# MCU.net
KiCad netlist of a schematic drawn in Altium Designer
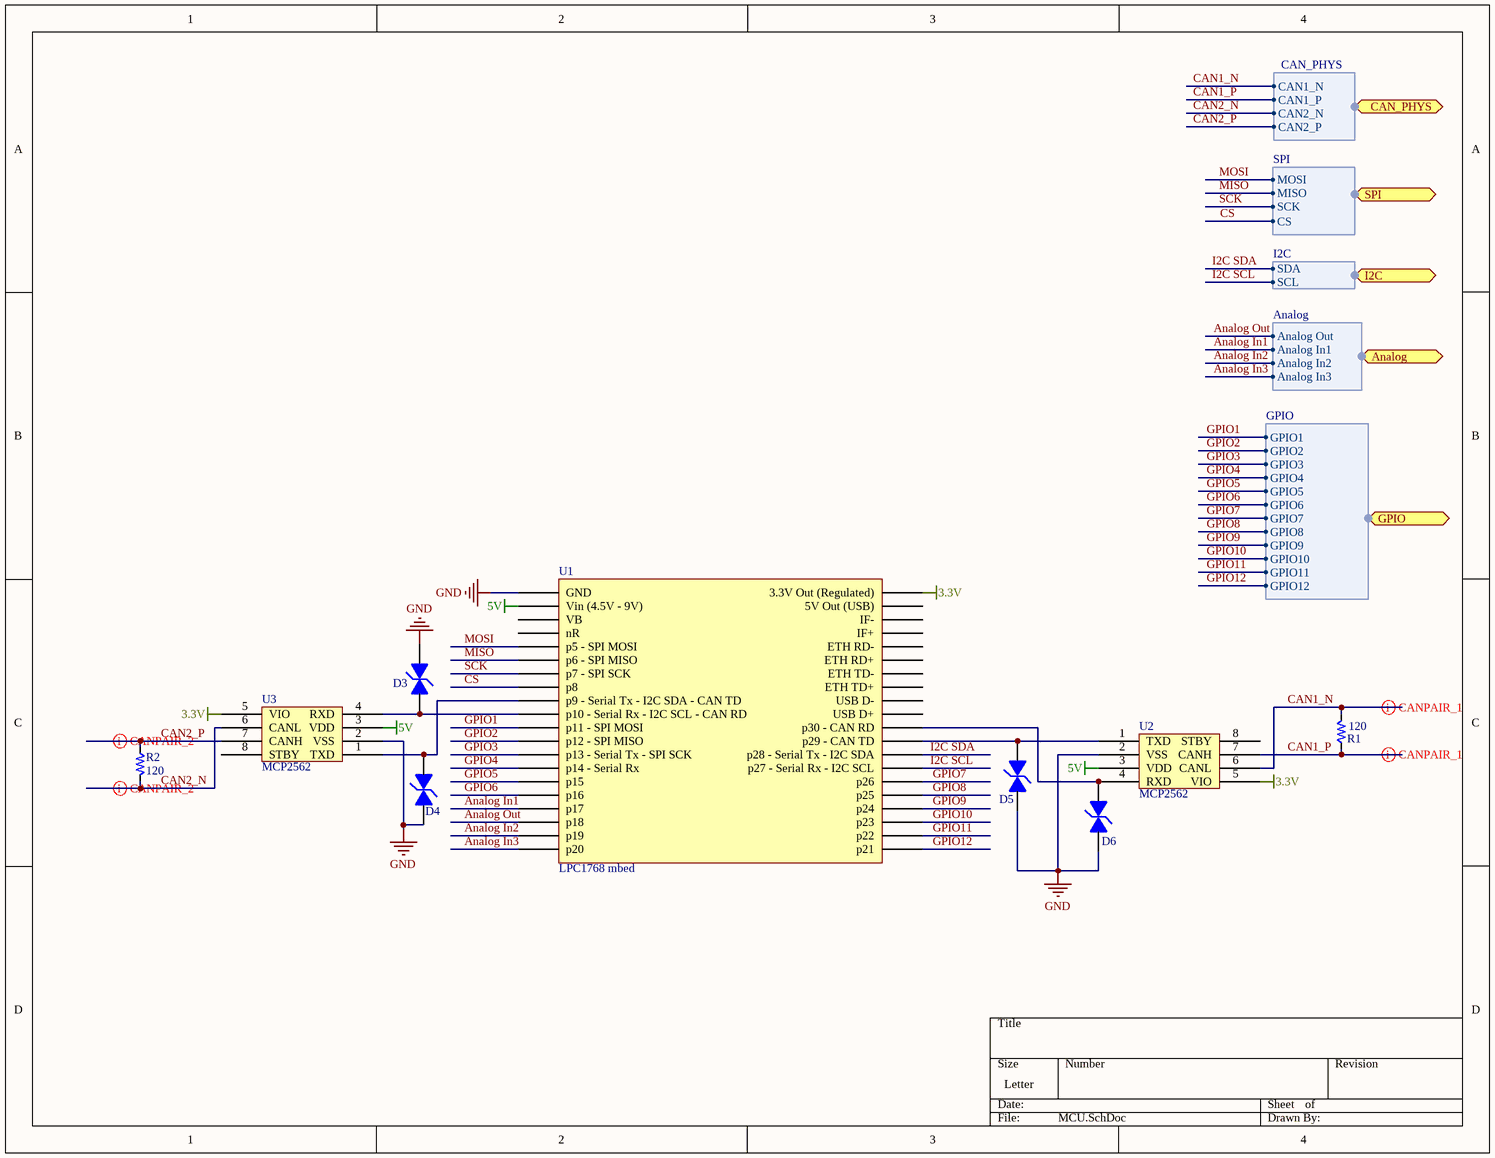
[diagram p0: MCU.SchDoc]

(export (version "E")
  (design (tool "Eeschema 10.0.6"))
  (components
    (comp (ref "D3")
      (value "TVS Diode")
      (footprint "TVS Diode")
      (fields (field (name "MANUFACTURER") "Bourns"))
      (libsource (lib "TVS Diode") (part "TVS Diode"))
    )
    (comp (ref "D4")
      (value "TVS Diode")
      (footprint "TVS Diode")
      (fields (field (name "MANUFACTURER") "Bourns"))
      (libsource (lib "TVS Diode") (part "TVS Diode"))
    )
    (comp (ref "D5")
      (value "TVS Diode")
      (footprint "TVS Diode")
      (fields (field (name "MANUFACTURER") "Bourns"))
      (libsource (lib "TVS Diode") (part "TVS Diode"))
    )
    (comp (ref "D6")
      (value "TVS Diode")
      (footprint "TVS Diode")
      (fields (field (name "MANUFACTURER") "Bourns"))
      (libsource (lib "TVS Diode") (part "TVS Diode"))
    )
    (comp (ref "R1")
      (value "120")
      (footprint "PCB_GENERIC_SMD_0603")
      (description "120 Ohms")
      (libsource (lib "SCH_GENERIC_RESISTOR_0603") (part "SCH_GENERIC_RESISTOR_0603"))
    )
    (comp (ref "R2")
      (value "120")
      (footprint "PCB_GENERIC_SMD_0603")
      (description "120 Ohms")
      (libsource (lib "SCH_GENERIC_RESISTOR_0603") (part "SCH_GENERIC_RESISTOR_0603"))
    )
    (comp (ref "U1")
      (value "LPC1768 mbed")
      (footprint "LPC 1768 mbed Layout")
      (libsource (lib "LPC1768_mbed_SCH") (part "LPC1768 mbed"))
    )
    (comp (ref "U2") (value "MCP2562") (footprint "MCP2562") (libsource (lib "") (part "MCP2562_1")))
    (comp (ref "U3") (value "MCP2562") (footprint "MCP2562") (libsource (lib "MCP2562_SCH") (part "MCP2562")))
  )
  (nets
    (net (code "6") (name "/Analog In1") (class "Default")
      (node (ref "U1") (pin "17") (pinfunction "p17_17") (pintype "passive"))
    )
    (net (code "7") (name "/Analog In2") (class "Default")
      (node (ref "U1") (pin "19") (pinfunction "p19_19") (pintype "passive"))
    )
    (net (code "8") (name "/Analog In3") (class "Default")
      (node (ref "U1") (pin "20") (pinfunction "p20_20") (pintype "passive"))
    )
    (net (code "9") (name "/Analog Out") (class "Default")
      (node (ref "U1") (pin "18") (pinfunction "p18_18") (pintype "passive"))
    )
    (net (code "10") (name "/CAN1_N") (class "Default")
      (node (ref "R1") (pin "2") (pinfunction "2_2") (pintype "passive"))
      (node (ref "U2") (pin "6") (pinfunction "CANL_6") (pintype "passive"))
    )
    (net (code "11") (name "/CAN1_P") (class "Default")
      (node (ref "R1") (pin "1") (pinfunction "1_1") (pintype "passive"))
      (node (ref "U2") (pin "7") (pinfunction "CANH_7") (pintype "passive"))
    )
    (net (code "12") (name "/CAN2_N") (class "Default")
      (node (ref "R2") (pin "2") (pinfunction "2_2") (pintype "passive"))
      (node (ref "U3") (pin "6") (pinfunction "CANL_6") (pintype "passive"))
    )
    (net (code "13") (name "/CAN2_P") (class "Default")
      (node (ref "R2") (pin "1") (pinfunction "1_1") (pintype "passive"))
      (node (ref "U3") (pin "7") (pinfunction "CANH_7") (pintype "passive"))
    )
    (net (code "14") (name "/CS") (class "Default")
      (node (ref "U1") (pin "8") (pinfunction "p8_8") (pintype "passive"))
    )
    (net (code "15") (name "/GPIO1") (class "Default")
      (node (ref "U1") (pin "11") (pinfunction "p11_-_SPI_MOSI_11") (pintype "passive"))
    )
    (net (code "16") (name "/GPIO2") (class "Default")
      (node (ref "U1") (pin "12") (pinfunction "p12_-_SPI_MISO_12") (pintype "passive"))
    )
    (net (code "17") (name "/GPIO3") (class "Default")
      (node (ref "U1") (pin "13") (pinfunction "p13_-_Serial_Tx_-_SPI_SCK_13") (pintype "passive"))
    )
    (net (code "18") (name "/GPIO4") (class "Default")
      (node (ref "U1") (pin "14") (pinfunction "p14_-_Serial_Rx_14") (pintype "passive"))
    )
    (net (code "19") (name "/GPIO5") (class "Default")
      (node (ref "U1") (pin "15") (pinfunction "p15_15") (pintype "passive"))
    )
    (net (code "20") (name "/GPIO6") (class "Default")
      (node (ref "U1") (pin "16") (pinfunction "p16_16") (pintype "passive"))
    )
    (net (code "21") (name "/GPIO7") (class "Default")
      (node (ref "U1") (pin "26") (pinfunction "p26_26") (pintype "passive"))
    )
    (net (code "22") (name "/GPIO8") (class "Default")
      (node (ref "U1") (pin "25") (pinfunction "p25_25") (pintype "passive"))
    )
    (net (code "23") (name "/GPIO9") (class "Default")
      (node (ref "U1") (pin "24") (pinfunction "p24_24") (pintype "passive"))
    )
    (net (code "24") (name "/GPIO10") (class "Default")
      (node (ref "U1") (pin "23") (pinfunction "p23_23") (pintype "passive"))
    )
    (net (code "25") (name "/GPIO11") (class "Default")
      (node (ref "U1") (pin "22") (pinfunction "p22_22") (pintype "passive"))
    )
    (net (code "26") (name "/GPIO12") (class "Default")
      (node (ref "U1") (pin "21") (pinfunction "p21_21") (pintype "passive"))
    )
    (net (code "27") (name "/I2C SCL") (class "Default")
      (node (ref "U1") (pin "27") (pinfunction "p27_-_Serial_Rx_-_I2C_SCL_27") (pintype "passive"))
    )
    (net (code "28") (name "/I2C SDA") (class "Default")
      (node (ref "U1") (pin "28") (pinfunction "p28_-_Serial_Tx_-_I2C_SDA_28") (pintype "passive"))
    )
    (net (code "29") (name "/MISO") (class "Default")
      (node (ref "U1") (pin "6") (pinfunction "p6_-_SPI_MISO_6") (pintype "passive"))
    )
    (net (code "30") (name "/MOSI") (class "Default")
      (node (ref "U1") (pin "5") (pinfunction "p5_-_SPI_MOSI_5") (pintype "passive"))
    )
    (net (code "31") (name "/SCK") (class "Default")
      (node (ref "U1") (pin "7") (pinfunction "p7_-_SPI_SCK_7") (pintype "passive"))
    )
    (net (code "37") (name "3.3V") (class "Default")
      (node (ref "U1") (pin "40") (pinfunction "3.3V_Out_(Regulated)_40") (pintype "passive"))
      (node (ref "U2") (pin "5") (pinfunction "VIO_5") (pintype "passive"))
      (node (ref "U3") (pin "5") (pinfunction "VIO_5") (pintype "passive"))
    )
    (net (code "38") (name "5V") (class "Default")
      (node (ref "U1") (pin "2") (pinfunction "Vin_(4.5V_-_9V)_2") (pintype "passive"))
      (node (ref "U2") (pin "3") (pinfunction "VDD_3") (pintype "passive"))
      (node (ref "U3") (pin "3") (pinfunction "VDD_3") (pintype "passive"))
    )
    (net (code "39") (name "GND") (class "Default")
      (node (ref "D3") (pin "2") (pintype "passive"))
      (node (ref "D4") (pin "2") (pintype "passive"))
      (node (ref "D5") (pin "1") (pintype "passive"))
      (node (ref "D6") (pin "1") (pintype "passive"))
      (node (ref "U1") (pin "1") (pinfunction "GND_1") (pintype "passive"))
      (node (ref "U2") (pin "2") (pinfunction "VSS_2") (pintype "passive"))
      (node (ref "U3") (pin "2") (pinfunction "VSS_2") (pintype "passive"))
    )
    (net (code "40") (name "Net-(U1-p9_-_Serial_Tx_-_I2C_SDA_-_CAN_TD)") (class "Default")
      (node (ref "D4") (pin "1") (pintype "passive"))
      (node (ref "U1") (pin "9") (pinfunction "p9_-_Serial_Tx_-_I2C_SDA_-_CAN_TD_9") (pintype "passive"))
      (node (ref "U3") (pin "1") (pinfunction "TXD_1") (pintype "passive"))
    )
    (net (code "41") (name "Net-(U1-p10_-_Serial_Rx_-_I2C_SCL_-_CAN_RD)") (class "Default")
      (node (ref "D3") (pin "1") (pintype "passive"))
      (node (ref "U1") (pin "10") (pinfunction "p10_-_Serial_Rx_-_I2C_SCL_-_CAN_RD_10") (pintype "passive"))
      (node (ref "U3") (pin "4") (pinfunction "RXD_4") (pintype "passive"))
    )
    (net (code "42") (name "Net-(U1-p29_-_CAN_TD)") (class "Default")
      (node (ref "D5") (pin "2") (pintype "passive"))
      (node (ref "U1") (pin "29") (pinfunction "p29_-_CAN_TD_29") (pintype "passive"))
      (node (ref "U2") (pin "1") (pinfunction "TXD_1") (pintype "passive"))
    )
    (net (code "43") (name "Net-(U1-p30_-_CAN_RD)") (class "Default")
      (node (ref "D6") (pin "2") (pintype "passive"))
      (node (ref "U1") (pin "30") (pinfunction "p30_-_CAN_RD_30") (pintype "passive"))
      (node (ref "U2") (pin "4") (pinfunction "RXD_4") (pintype "passive"))
    )
    (net (code "44") (name "unconnected-(U1-5V_Out_(USB)-Pad39)") (class "Default")
      (node (ref "U1") (pin "39") (pinfunction "5V_Out_(USB)_39") (pintype "passive"))
    )
    (net (code "45") (name "unconnected-(U1-ETH_RD+-Pad35)") (class "Default")
      (node (ref "U1") (pin "35") (pinfunction "ETH_RD+_35") (pintype "passive"))
    )
    (net (code "46") (name "unconnected-(U1-ETH_RD--Pad36)") (class "Default")
      (node (ref "U1") (pin "36") (pinfunction "ETH_RD-_36") (pintype "passive"))
    )
    (net (code "47") (name "unconnected-(U1-ETH_TD+-Pad33)") (class "Default")
      (node (ref "U1") (pin "33") (pinfunction "ETH_TD+_33") (pintype "passive"))
    )
    (net (code "48") (name "unconnected-(U1-ETH_TD--Pad34)") (class "Default")
      (node (ref "U1") (pin "34") (pinfunction "ETH_TD-_34") (pintype "passive"))
    )
    (net (code "49") (name "unconnected-(U1-IF+-Pad37)") (class "Default")
      (node (ref "U1") (pin "37") (pinfunction "IF+_37") (pintype "passive"))
    )
    (net (code "50") (name "unconnected-(U1-IF--Pad38)") (class "Default")
      (node (ref "U1") (pin "38") (pinfunction "IF-_38") (pintype "passive"))
    )
    (net (code "51") (name "unconnected-(U1-USB_D+-Pad31)") (class "Default")
      (node (ref "U1") (pin "31") (pinfunction "USB_D+_31") (pintype "passive"))
    )
    (net (code "52") (name "unconnected-(U1-USB_D--Pad32)") (class "Default")
      (node (ref "U1") (pin "32") (pinfunction "USB_D-_32") (pintype "passive"))
    )
    (net (code "53") (name "unconnected-(U1-VB-Pad3)") (class "Default")
      (node (ref "U1") (pin "3") (pinfunction "VB_3") (pintype "passive"))
    )
    (net (code "54") (name "unconnected-(U1-nR-Pad4)") (class "Default")
      (node (ref "U1") (pin "4") (pinfunction "nR_4") (pintype "passive"))
    )
    (net (code "55") (name "unconnected-(U2-STBY-Pad8)") (class "Default")
      (node (ref "U2") (pin "8") (pinfunction "STBY_8") (pintype "passive"))
    )
    (net (code "56") (name "unconnected-(U3-STBY-Pad8)") (class "Default")
      (node (ref "U3") (pin "8") (pinfunction "STBY_8") (pintype "passive"))
    )
  )
)
